# io-matrix.net
KiCad netlist of a schematic drawn in Altium Designer
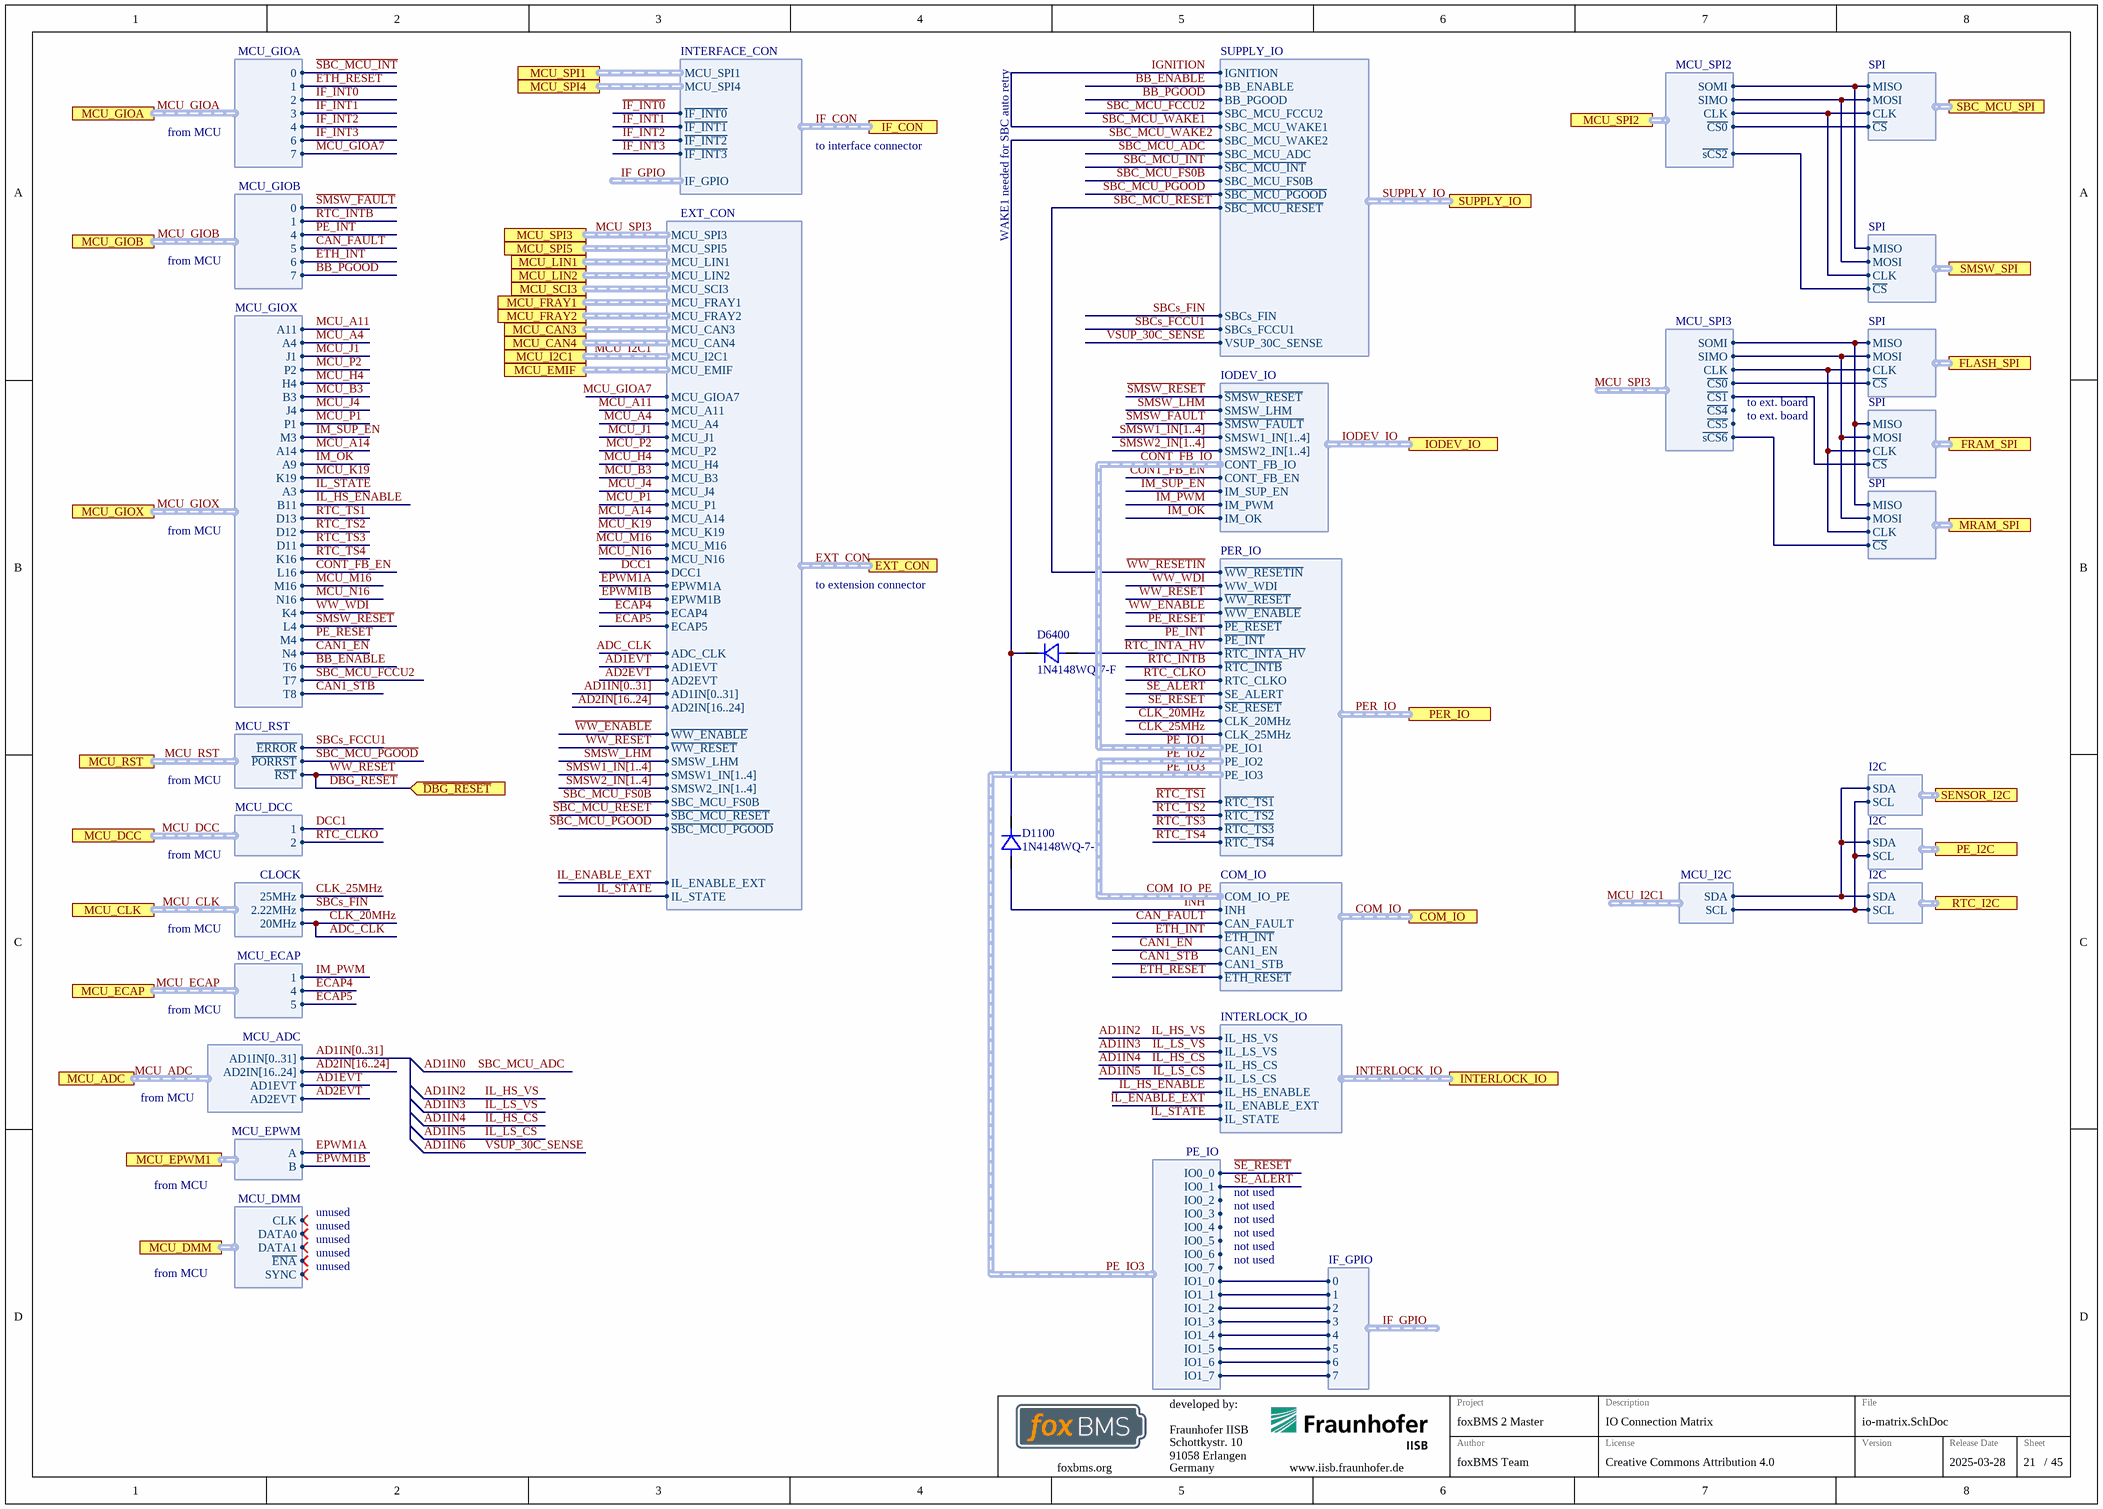
[diagram p0: io-matrix.SchDoc]

(export (version "E")
  (design (tool "Eeschema 10.0.6"))
  (components
    (comp (ref "D1100")
      (value "1N4148WQ-7-F")
      (footprint "SOD-123_CASE-425-04-ISSUE-G")
      (description "Diode")
      (fields (field (name "MANUFACTURER") "Diodes Inc."))
      (libsource (lib "OE750") (part "D"))
    )
    (comp (ref "D6400")
      (value "1N4148WQ-7-F")
      (footprint "SOD-123_CASE-425-04-ISSUE-G")
      (description "Diode")
      (fields (field (name "MANUFACTURER") "Diodes Inc."))
      (libsource (lib "OE750") (part "D"))
    )
  )
  (nets
    (net (code "125") (name "/INH") (class "Default")
      (node (ref "D1100") (pin "2") (pinfunction "A_2") (pintype "passive"))
    )
    (net (code "164") (name "/RTC_INTA_HV") (class "Default")
      (node (ref "D6400") (pin "2") (pinfunction "A_2") (pintype "passive"))
    )
    (net (code "175") (name "/SBC_MCU_WAKE2") (class "Default")
      (node (ref "D1100") (pin "1") (pinfunction "K_1") (pintype "passive"))
      (node (ref "D6400") (pin "1") (pinfunction "K_1") (pintype "passive"))
    )
  )
)
